# TSL230_v10.net
KiCad netlist of a schematic drawn in EAGLE
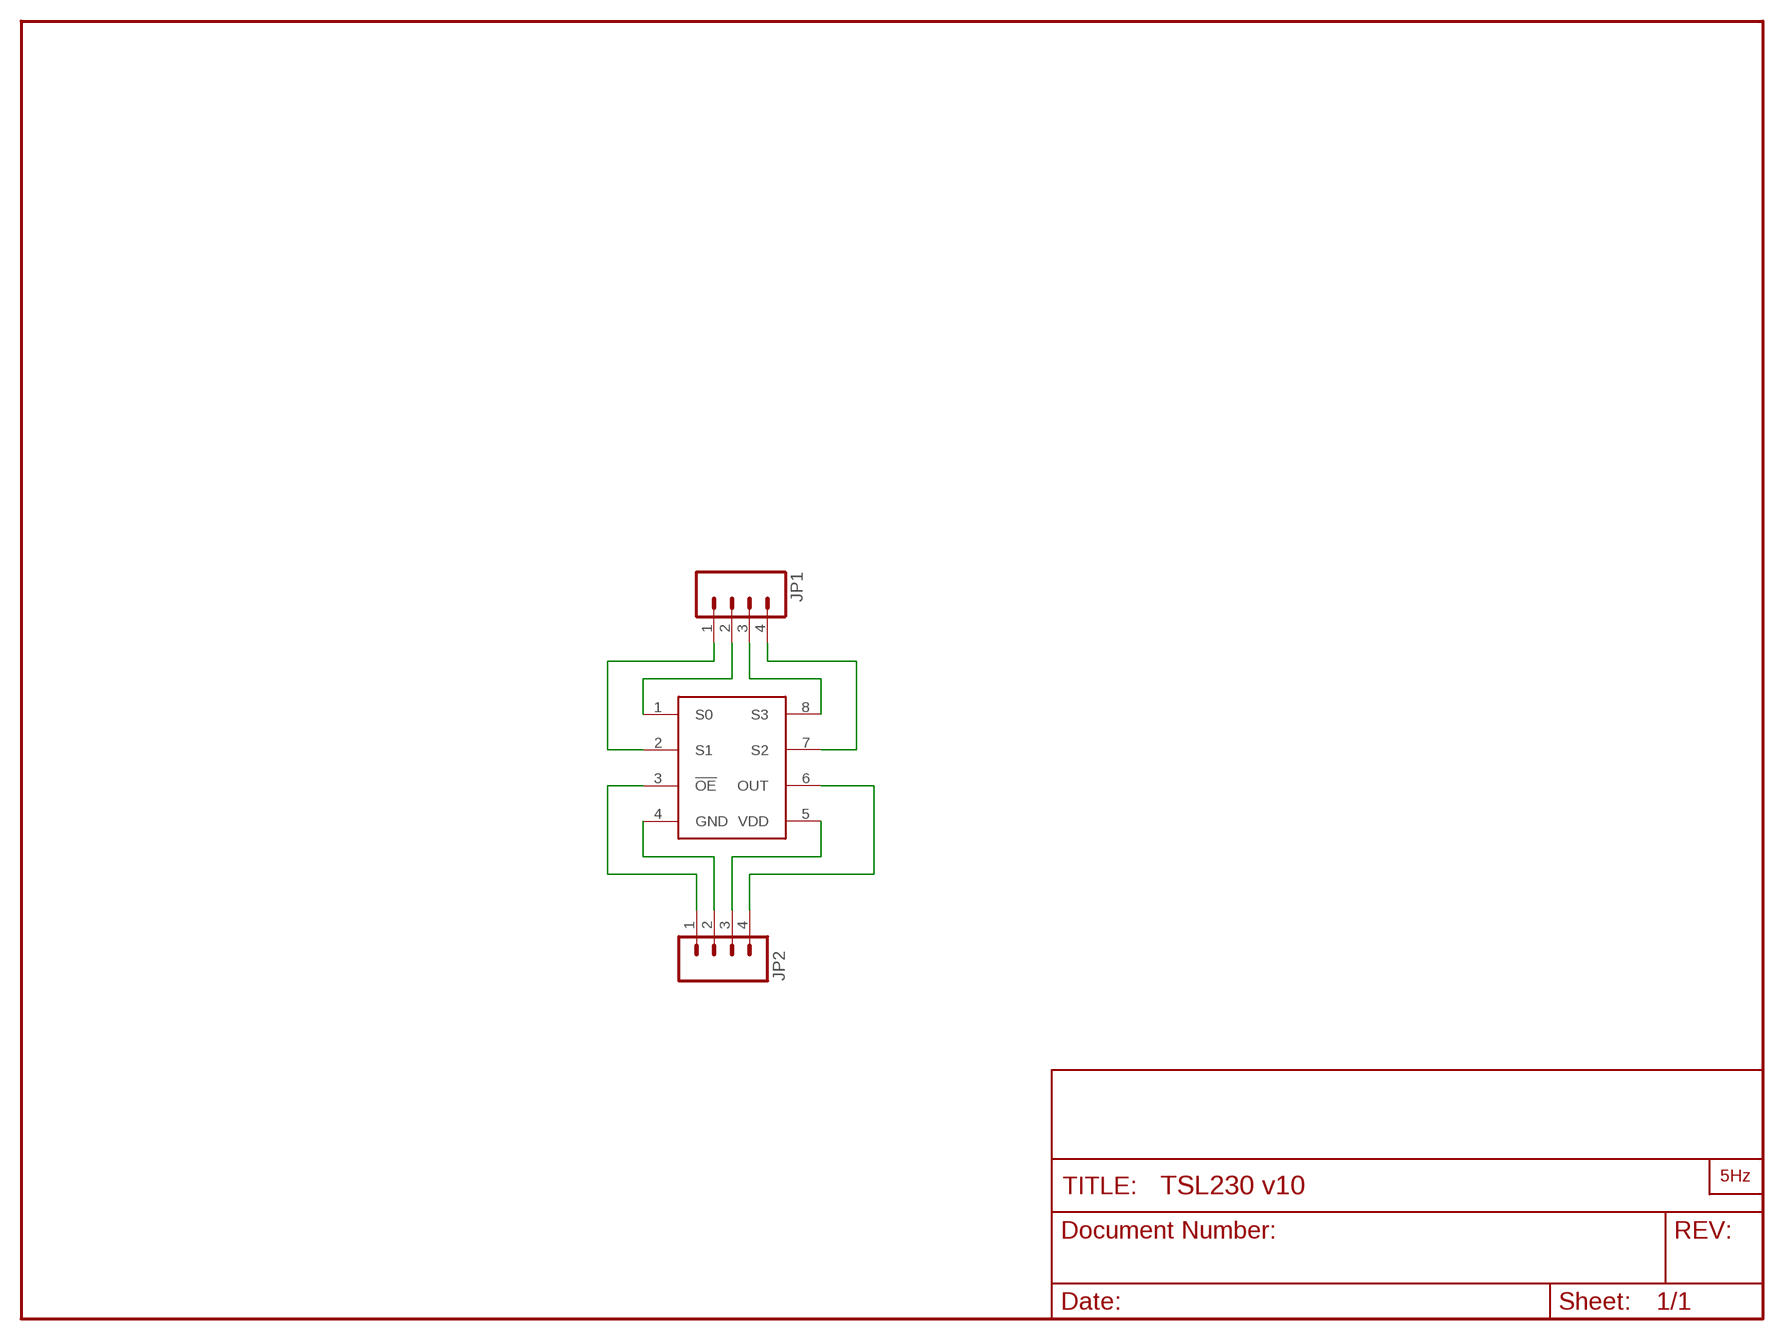
[diagram p0: schematic, sheet 1]

(export (version "E")
  (design (tool "Eeschema 10.0.6"))
  (components
    (comp (ref "JP1")
      (value "M04PTH")
      (footprint "eagle-import:1X04")
      (libsource (lib "eagle-import") (part "M04PTH"))
    )
    (comp (ref "JP2")
      (value "M04PTH")
      (footprint "eagle-import:1X04")
      (libsource (lib "eagle-import") (part "M04PTH"))
    )
    (comp (ref "U$1")
      (value "TSL230RD")
      (footprint "eagle-import:SOIC8")
      (libsource (lib "eagle-import") (part "TSL230RD"))
    )
    (comp (ref "U$2")
      (value "LOGO2_SILKL5MM")
      (footprint "eagle-import:LARGO2_5MM")
      (libsource (lib "eagle-import") (part "LOGO2_SILKL5MM"))
    )
  )
  (nets
    (net (code "1") (name "Net-(U$1-GND)") (class "Default")
      (node (ref "JP2") (pin "2") (pinfunction "2_2") (pintype "passive"))
      (node (ref "U$1") (pin "4") (pinfunction "GND_4") (pintype "bidirectional"))
    )
    (net (code "2") (name "Net-(U$1-OUT)") (class "Default")
      (node (ref "JP2") (pin "4") (pinfunction "4_4") (pintype "passive"))
      (node (ref "U$1") (pin "6") (pinfunction "OUT_6") (pintype "bidirectional"))
    )
    (net (code "3") (name "Net-(U$1-S0)") (class "Default")
      (node (ref "JP1") (pin "2") (pinfunction "2_2") (pintype "passive"))
      (node (ref "U$1") (pin "1") (pinfunction "S0_1") (pintype "bidirectional"))
    )
    (net (code "4") (name "Net-(U$1-S1)") (class "Default")
      (node (ref "JP1") (pin "1") (pinfunction "1_1") (pintype "passive"))
      (node (ref "U$1") (pin "2") (pinfunction "S1_2") (pintype "bidirectional"))
    )
    (net (code "5") (name "Net-(U$1-S2)") (class "Default")
      (node (ref "JP1") (pin "4") (pinfunction "4_4") (pintype "passive"))
      (node (ref "U$1") (pin "7") (pinfunction "S2_7") (pintype "bidirectional"))
    )
    (net (code "6") (name "Net-(U$1-S3)") (class "Default")
      (node (ref "JP1") (pin "3") (pinfunction "3_3") (pintype "passive"))
      (node (ref "U$1") (pin "8") (pinfunction "S3_8") (pintype "bidirectional"))
    )
    (net (code "7") (name "Net-(U$1-VDD)") (class "Default")
      (node (ref "JP2") (pin "3") (pinfunction "3_3") (pintype "passive"))
      (node (ref "U$1") (pin "5") (pinfunction "VDD_5") (pintype "bidirectional"))
    )
    (net (code "8") (name "Net-(U$1-~{OE})") (class "Default")
      (node (ref "JP2") (pin "1") (pinfunction "1_1") (pintype "passive"))
      (node (ref "U$1") (pin "3") (pinfunction "~{OE}_3") (pintype "bidirectional"))
    )
  )
)
